# C210_0002_NORA_Module.net
KiCad netlist of a schematic drawn in Altium Designer
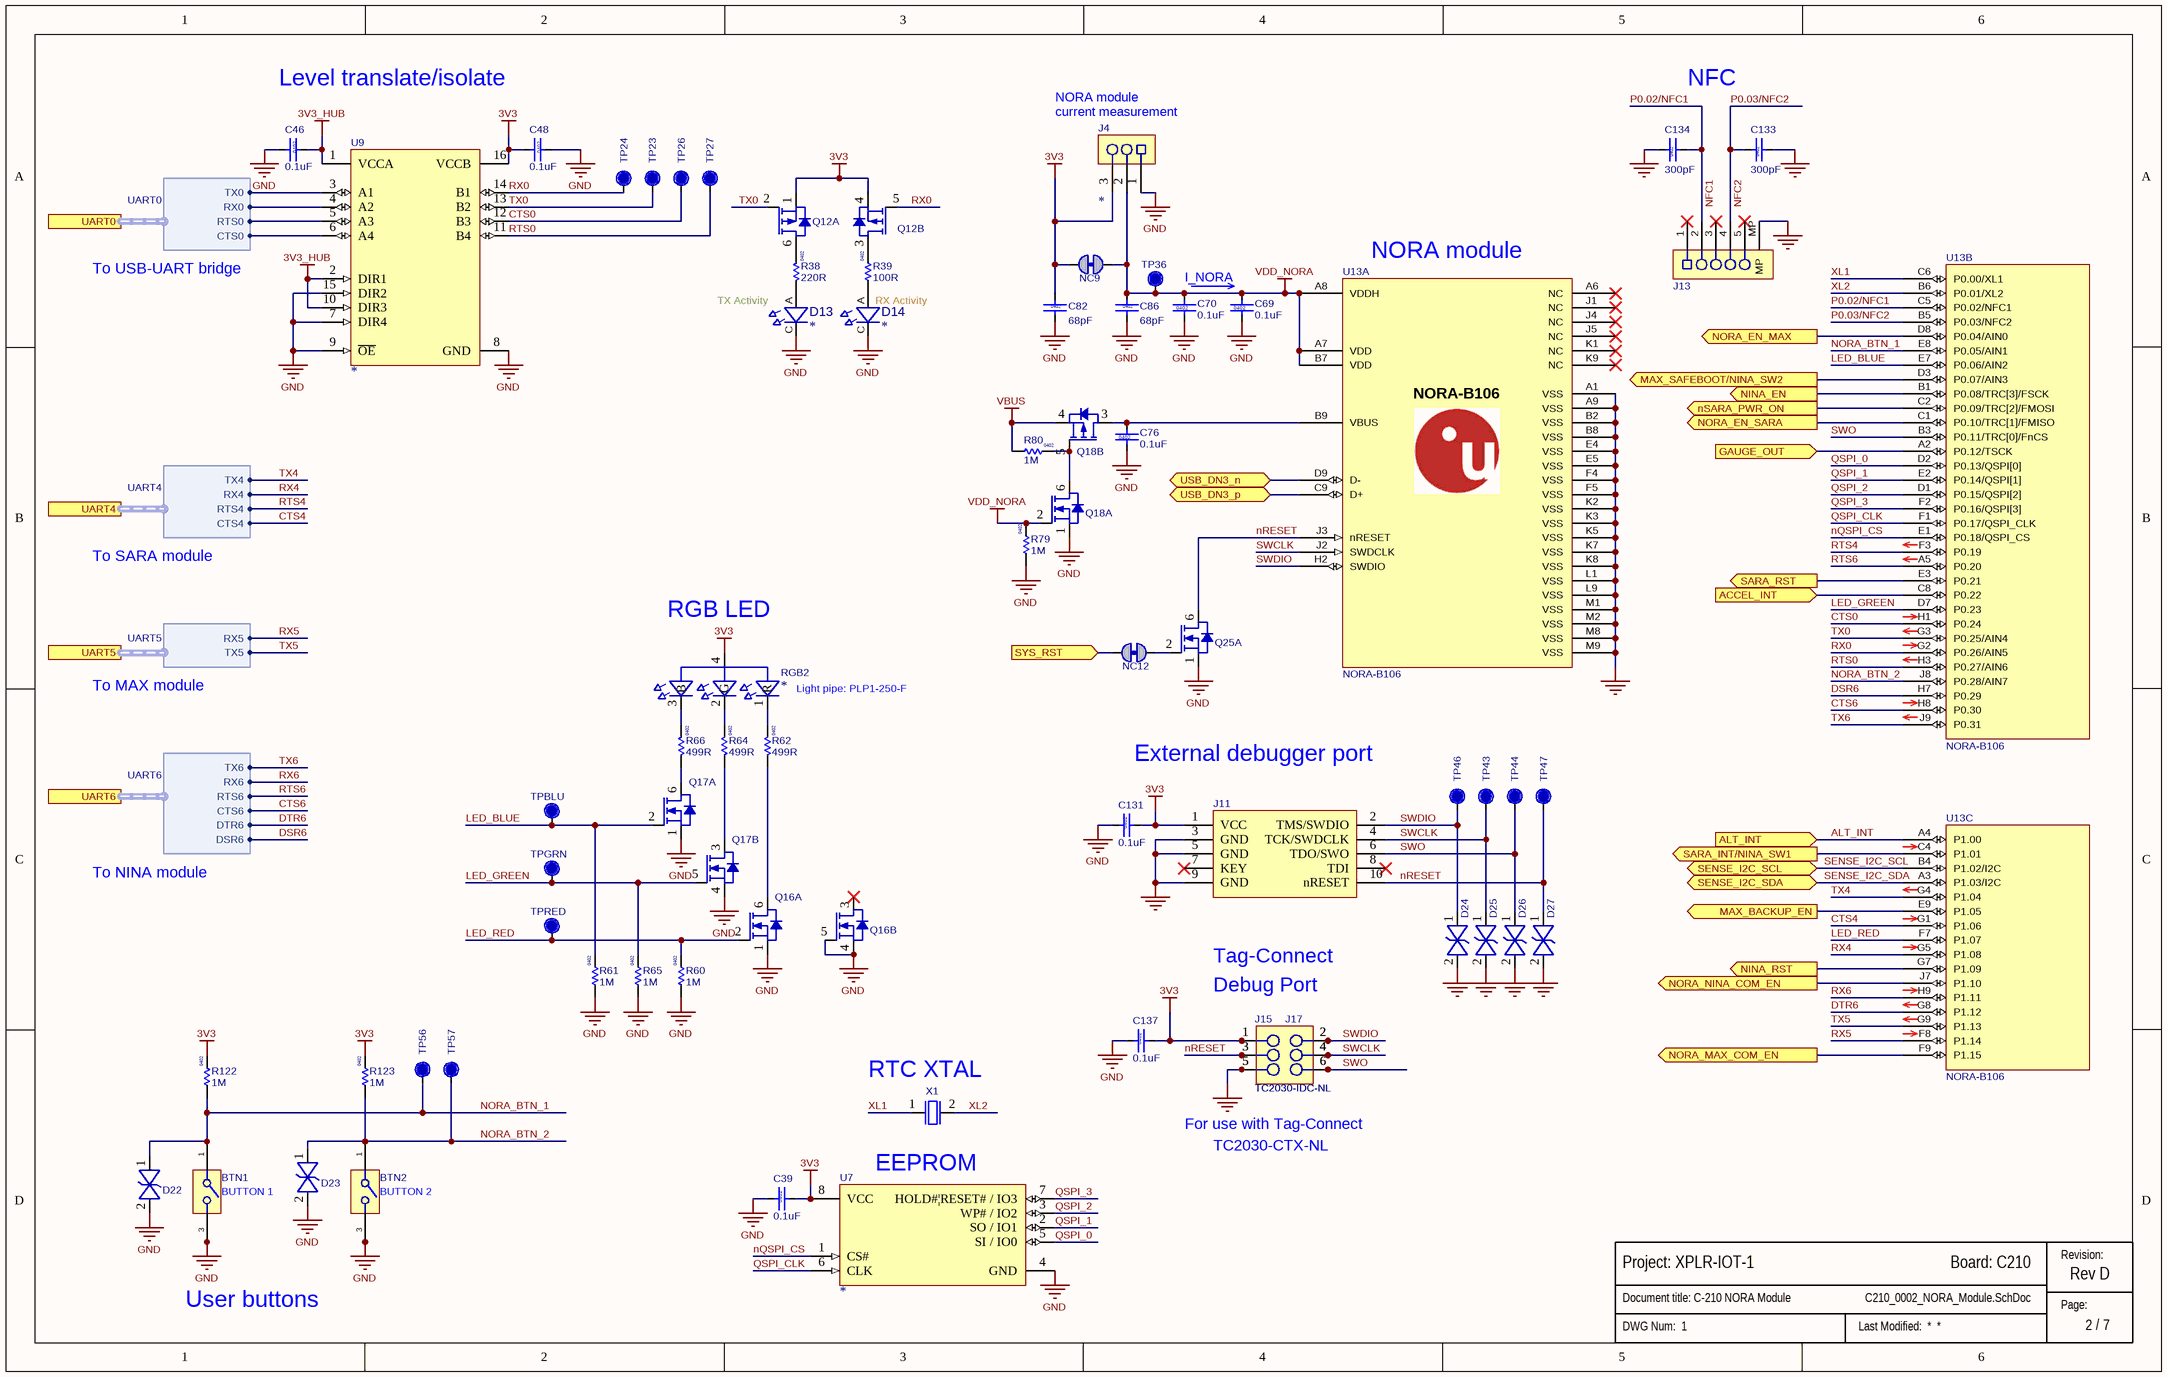
[diagram p0: C210_0002_NORA_Module.SchDoc]

(export (version "E")
  (design (tool "Eeschema 10.0.6"))
  (components
    (comp (ref "BTN1")
      (value "TL6120DF300QG")
      (footprint "TL6120DF300QG")
      (description "Button, Tactile, SPST, NO, SMT, Vert")
      (fields (field (name "VOLTAGE") "None"))
      (libsource (lib "TL6120DF300QG") (part "TL6120DF300QG"))
    )
    (comp (ref "BTN2")
      (value "TL6120DF300QG")
      (footprint "TL6120DF300QG")
      (description "Button, Tactile, SPST, NO, SMT, Vert")
      (fields (field (name "VOLTAGE") "None"))
      (libsource (lib "TL6120DF300QG") (part "TL6120DF300QG"))
    )
    (comp (ref "C39")
      (value "0.1uF")
      (footprint "Cap 0402 HD")
      (description "Cap, Ceramic 0.1uF 10V 10% X5R 0402")
      (fields
        (field (name "SIZE") "0402")
        (field (name "PART NUMBER") "120-00016")
        (field (name "MANUFACTURER") "Murata Electronics North America")
      )
      (libsource (lib "Arena_Parts_DB_Lib") (part "Cap Chip"))
    )
    (comp (ref "C46")
      (value "0.1uF")
      (footprint "Cap 0402 HD")
      (description "Cap, Ceramic 0.1uF 10V 10% X5R 0402")
      (fields
        (field (name "SIZE") "0402")
        (field (name "PART NUMBER") "120-00016")
        (field (name "MANUFACTURER") "Murata Electronics North America")
      )
      (libsource (lib "Arena_Parts_DB_Lib") (part "Cap Chip"))
    )
    (comp (ref "C48")
      (value "0.1uF")
      (footprint "Cap 0402 HD")
      (description "Cap, Ceramic 0.1uF 10V 10% X5R 0402")
      (fields
        (field (name "SIZE") "0402")
        (field (name "PART NUMBER") "120-00016")
        (field (name "MANUFACTURER") "Murata Electronics North America")
      )
      (libsource (lib "Arena_Parts_DB_Lib") (part "Cap Chip"))
    )
    (comp (ref "C69")
      (value "0.1uF")
      (footprint "Cap 0402 HD")
      (description "Cap, Ceramic 0.1uF 10V 10% X5R 0402")
      (fields
        (field (name "SIZE") "0402")
        (field (name "PART NUMBER") "120-00016")
        (field (name "MANUFACTURER") "Murata Electronics North America")
      )
      (libsource (lib "Arena_Parts_DB_Lib") (part "Cap Chip"))
    )
    (comp (ref "C70")
      (value "0.1uF")
      (footprint "Cap 0402 HD")
      (description "Cap, Ceramic 0.1uF 10V 10% X5R 0402")
      (fields
        (field (name "SIZE") "0402")
        (field (name "PART NUMBER") "120-00016")
        (field (name "MANUFACTURER") "Murata Electronics North America")
      )
      (libsource (lib "Arena_Parts_DB_Lib") (part "Cap Chip"))
    )
    (comp (ref "C76")
      (value "0.1uF")
      (footprint "Cap 0402 HD")
      (description "Cap, Ceramic 0.1uF 10V 10% X5R 0402")
      (fields
        (field (name "SIZE") "0402")
        (field (name "PART NUMBER") "120-00016")
        (field (name "MANUFACTURER") "Murata Electronics North America")
      )
      (libsource (lib "Arena_Parts_DB_Lib") (part "Cap Chip"))
    )
    (comp (ref "C82")
      (value "68pF")
      (footprint "Cap 0402 HD")
      (description "Cap, Ceramic, 68pF, 50V, 1%, NP0, 0402")
      (fields
        (field (name "SIZE") "0402")
        (field (name "PART NUMBER") "120-00047")
        (field (name "TOLERANCE") "+/- 1%")
      )
      (libsource (lib "Arena_Parts_DB_Lib") (part "Cap Chip"))
    )
    (comp (ref "C86")
      (value "68pF")
      (footprint "Cap 0402 HD")
      (description "Cap, Ceramic, 68pF, 50V, 1%, NP0, 0402")
      (fields
        (field (name "SIZE") "0402")
        (field (name "PART NUMBER") "120-00047")
        (field (name "TOLERANCE") "+/- 1%")
      )
      (libsource (lib "Arena_Parts_DB_Lib") (part "Cap Chip"))
    )
    (comp (ref "C131")
      (value "0.1uF")
      (footprint "Cap 0402 HD")
      (description "Cap, Ceramic 0.1uF 10V 10% X5R 0402")
      (fields
        (field (name "SIZE") "0402")
        (field (name "PART NUMBER") "120-00016")
        (field (name "MANUFACTURER") "Murata Electronics North America")
      )
      (libsource (lib "Arena_Parts_DB_Lib") (part "Cap Chip"))
    )
    (comp (ref "C133")
      (value "300pF")
      (footprint "Cap 0402 HD")
      (description "Cap, Ceramic 300pF 50V 5% NP0 0402")
      (fields
        (field (name "SIZE") "0402")
        (field (name "PART NUMBER") "120-00099")
        (field (name "MANUFACTURER") "Murata Electronics North America")
      )
      (libsource (lib "Arena_Parts_DB_Lib") (part "Cap Chip"))
    )
    (comp (ref "C134")
      (value "300pF")
      (footprint "Cap 0402 HD")
      (description "Cap, Ceramic 300pF 50V 5% NP0 0402")
      (fields
        (field (name "SIZE") "0402")
        (field (name "PART NUMBER") "120-00099")
        (field (name "MANUFACTURER") "Murata Electronics North America")
      )
      (libsource (lib "Arena_Parts_DB_Lib") (part "Cap Chip"))
    )
    (comp (ref "C137")
      (value "0.1uF")
      (footprint "Cap 0402 HD")
      (description "Cap, Ceramic 0.1uF 10V 10% X5R 0402")
      (fields
        (field (name "SIZE") "0402")
        (field (name "PART NUMBER") "120-00016")
        (field (name "MANUFACTURER") "Murata Electronics North America")
      )
      (libsource (lib "Arena_Parts_DB_Lib") (part "Cap Chip"))
    )
    (comp (ref "D13")
      (value "115-00019")
      (footprint "LTST-C190KGKT")
      (description "DIODE, LED, SMT, GREEN, CLEAR LENS, 2.0V 20mA, 0603")
      (fields (field (name "VOLTAGE") "2.0V") (field (name "COLOR") "*"))
      (libsource (lib "LTST-C190KGKT") (part "LTST-C190KGKT"))
    )
    (comp (ref "D14")
      (value "LTST-C190YKT")
      (footprint "LTST-C190YKT")
      (description "DIODE, LED, SMT, YELLOW, CLEAR LENS, 2.1V 10mA, 0603")
      (fields (field (name "VOLTAGE") "2.1V") (field (name "COLOR") "*"))
      (libsource (lib "LTST-C190YKT") (part "LTST-C190YKT"))
    )
    (comp (ref "D22")
      (value "110-00041")
      (footprint "SOD-523_ALT")
      (description "Diode TVS 5VWM BiDIR SOD523")
      (fields (field (name "VOLTAGE") "5VWM"))
      (libsource (lib "Arena_Parts_DB_Lib") (part "Diode_TVS"))
    )
    (comp (ref "D23")
      (value "110-00041")
      (footprint "SOD-523_ALT")
      (description "Diode TVS 5VWM BiDIR SOD523")
      (fields (field (name "VOLTAGE") "5VWM"))
      (libsource (lib "Arena_Parts_DB_Lib") (part "Diode_TVS"))
    )
    (comp (ref "D24")
      (value "110-00041")
      (footprint "SOD-523_ALT")
      (description "Diode TVS 5VWM BiDIR SOD523")
      (fields (field (name "VOLTAGE") "5VWM"))
      (libsource (lib "Arena_Parts_DB_Lib") (part "Diode_TVS"))
    )
    (comp (ref "D25")
      (value "110-00041")
      (footprint "SOD-523_ALT")
      (description "Diode TVS 5VWM BiDIR SOD523")
      (fields (field (name "VOLTAGE") "5VWM"))
      (libsource (lib "Arena_Parts_DB_Lib") (part "Diode_TVS"))
    )
    (comp (ref "D26")
      (value "110-00041")
      (footprint "SOD-523_ALT")
      (description "Diode TVS 5VWM BiDIR SOD523")
      (fields (field (name "VOLTAGE") "5VWM"))
      (libsource (lib "Arena_Parts_DB_Lib") (part "Diode_TVS"))
    )
    (comp (ref "D27")
      (value "110-00041")
      (footprint "SOD-523_ALT")
      (description "Diode TVS 5VWM BiDIR SOD523")
      (fields (field (name "VOLTAGE") "5VWM"))
      (libsource (lib "Arena_Parts_DB_Lib") (part "Diode_TVS"))
    )
    (comp (ref "J4")
      (value "130-00105")
      (footprint "HDR-0.1P-3Pin-1Row-SMT")
      (description "Header, 0.100\" Pitch, 3 Pin, Vertical SMT, Black")
      (fields (field (name "MANUFACTURER P/N") "*") (field (name "VOLTAGE") "None"))
      (libsource (lib "Arena_Parts_DB_Lib") (part "CON-3Pin_1Row"))
    )
    (comp (ref "J11")
      (value "FTSH-105-01-F-DH-A-C - JTAG")
      (footprint "FTSH-105-01-F-DH-A-C")
      (description "Header 0.05\" 10Pin 2Row SMD, RA, Black")
      (libsource (lib "FTSH-105-01-F-DH-A-C") (part "FTSH-105-01-F-DH-A-C - JTAG"))
    )
    (comp (ref "J13")
      (value "~")
      (footprint "AVX/Kyocera - 046284005001846")
      (description "CON FFC/FPC 0.50mm 5Pos R/A, 046284005001846")
      (fields (field (name "VOLTAGE") "50V"))
      (libsource (lib "046284005001846") (part "CON-5Pin_1Row-046284005001846"))
    )
    (comp (ref "J15")
      (value "TC2030-IDC-NLDNP")
      (footprint "TC2030-IDC-NL")
      (description "CON PADS FOR CBL PLUG-OF-NAILS 6-PIN NO LEGS")
      (fields
        (field (name "PART NUMBER") "TC2030-IDC-NL")
        (field (name "MANUFACTURER") "TAG Connect")
        (field (name "MANUFACTURER P/N") "TC2030-IDC-NL")
        (field (name "ADDED BY") "emoo")
      )
      (libsource (lib "PCB_Misc") (part "CON-6Pin_2Row_ALT"))
    )
    (comp (ref "J17")
      (value "TC2030-IDC-NLDNP")
      (footprint "TC2030-IDC-NL No Hole")
      (description "CON PADS FOR CBL PLUG-OF-NAILS 6-PIN NO LEGS")
      (fields
        (field (name "PART NUMBER") "TC2030-IDC-NL")
        (field (name "MANUFACTURER") "TAG Connect")
        (field (name "MANUFACTURER P/N") "TC2030-IDC-NL")
        (field (name "ADDED BY") "emoo")
      )
      (libsource (lib "PCB_Misc") (part "CON-6Pin_2Row_ALT"))
    )
    (comp (ref "NC9")
      (value "Solderbridge-ShortDNP")
      (footprint "Solderbridge-Short")
      (description "Solderbridge-Short")
      (fields (field (name "ADDED BY") "Paul B"))
      (libsource (lib "PCB_Misc") (part "Solderbridge-Short"))
    )
    (comp (ref "NC12")
      (value "Solderbridge-ShortDNP")
      (footprint "Solderbridge-Short")
      (description "Solderbridge-Short")
      (fields (field (name "ADDED BY") "Paul B"))
      (libsource (lib "PCB_Misc") (part "Solderbridge-Short"))
    )
    (comp (ref "Q12")
      (value "FDY2000PZ")
      (footprint "FDY2000PZ")
      (description "MOSFET DUAL P-CH 20V SOT-563, -350mA")
      (fields (field (name "VOLTAGE") "20V"))
      (libsource (lib "FDY2000PZ") (part "MOSFET-Dual-P_Chan"))
    )
    (comp (ref "Q16")
      (value "140-00016")
      (footprint "SOT-563")
      (description "MOSFET 2N-CH 20V 0.8A, SOT-563")
      (fields (field (name "VOLTAGE") "20V"))
      (libsource (lib "Arena_Parts_DB_Lib") (part "MOSFET-N-Dual"))
    )
    (comp (ref "Q17")
      (value "140-00016")
      (footprint "SOT-563")
      (description "MOSFET 2N-CH 20V 0.8A, SOT-563")
      (fields (field (name "VOLTAGE") "20V"))
      (libsource (lib "Arena_Parts_DB_Lib") (part "MOSFET-N-Dual"))
    )
    (comp (ref "Q18")
      (value "140-00030")
      (footprint "SOT-563")
      (description "MOSFET N/P-CH 20V SOT-563, 540 mA, −430 mA")
      (fields (field (name "VOLTAGE") "20V"))
      (libsource (lib "Arena_Parts_DB_Lib") (part "MOSFET-N-P_Pair"))
    )
    (comp (ref "Q25")
      (value "140-00016")
      (footprint "SOT-563")
      (description "MOSFET 2N-CH 20V 0.8A, SOT-563")
      (fields (field (name "VOLTAGE") "20V"))
      (libsource (lib "Arena_Parts_DB_Lib") (part "MOSFET-N-Dual"))
    )
    (comp (ref "R38")
      (value "220R")
      (footprint "RES 0402 HD")
      (description "Resistor, 220ohm, 5%, 1/16W, 0402.")
      (fields
        (field (name "SIZE") "0402")
        (field (name "PART NUMBER") "180-00098")
        (field (name "MANUFACTURER") "Panasonic Electronic Components")
      )
      (libsource (lib "Arena_Parts_DB_Lib") (part "Res sm"))
    )
    (comp (ref "R39")
      (value "100R")
      (footprint "RES 0402 HD")
      (description "Resistor, 100ohm, 1%, 1/16W, 0402.")
      (fields
        (field (name "SIZE") "0402")
        (field (name "PART NUMBER") "180-00051")
        (field (name "POWER") "1/16W")
      )
      (libsource (lib "Arena_Parts_DB_Lib") (part "Res sm"))
    )
    (comp (ref "R60")
      (value "1M")
      (footprint "RES 0402 HD")
      (description "Resistor 1M ohm 1%, 1/16W, 0402")
      (fields
        (field (name "SIZE") "0402")
        (field (name "PART NUMBER") "180-00054")
        (field (name "POWER") "1/16W")
      )
      (libsource (lib "Arena_Parts_DB_Lib") (part "Res sm"))
    )
    (comp (ref "R61")
      (value "1M")
      (footprint "RES 0402 HD")
      (description "Resistor 1M ohm 1%, 1/16W, 0402")
      (fields
        (field (name "SIZE") "0402")
        (field (name "PART NUMBER") "180-00054")
        (field (name "POWER") "1/16W")
      )
      (libsource (lib "Arena_Parts_DB_Lib") (part "Res sm"))
    )
    (comp (ref "R62")
      (value "499R")
      (footprint "RES 0402 HD")
      (description "Resistor, 499ohm, 1%, 1/16W, 0402")
      (fields
        (field (name "SIZE") "0402")
        (field (name "PART NUMBER") "180-00031")
        (field (name "MANUFACTURER") "Rohm Semiconductor")
      )
      (libsource (lib "Arena_Parts_DB_Lib") (part "Res sm"))
    )
    (comp (ref "R64")
      (value "499R")
      (footprint "RES 0402 HD")
      (description "Resistor, 499ohm, 1%, 1/16W, 0402")
      (fields
        (field (name "SIZE") "0402")
        (field (name "PART NUMBER") "180-00031")
        (field (name "MANUFACTURER") "Rohm Semiconductor")
      )
      (libsource (lib "Arena_Parts_DB_Lib") (part "Res sm"))
    )
    (comp (ref "R65")
      (value "1M")
      (footprint "RES 0402 HD")
      (description "Resistor 1M ohm 1%, 1/16W, 0402")
      (fields
        (field (name "SIZE") "0402")
        (field (name "PART NUMBER") "180-00054")
        (field (name "POWER") "1/16W")
      )
      (libsource (lib "Arena_Parts_DB_Lib") (part "Res sm"))
    )
    (comp (ref "R66")
      (value "499R")
      (footprint "RES 0402 HD")
      (description "Resistor, 499ohm, 1%, 1/16W, 0402")
      (fields
        (field (name "SIZE") "0402")
        (field (name "PART NUMBER") "180-00031")
        (field (name "MANUFACTURER") "Rohm Semiconductor")
      )
      (libsource (lib "Arena_Parts_DB_Lib") (part "Res sm"))
    )
    (comp (ref "R79")
      (value "1M")
      (footprint "RES 0402 HD")
      (description "Resistor 1M ohm 1%, 1/16W, 0402")
      (fields
        (field (name "SIZE") "0402")
        (field (name "PART NUMBER") "180-00054")
        (field (name "POWER") "1/16W")
      )
      (libsource (lib "Arena_Parts_DB_Lib") (part "Res sm"))
    )
    (comp (ref "R80")
      (value "1M")
      (footprint "RES 0402 HD")
      (description "Resistor 1M ohm 1%, 1/16W, 0402")
      (fields
        (field (name "SIZE") "0402")
        (field (name "PART NUMBER") "180-00054")
        (field (name "POWER") "1/16W")
      )
      (libsource (lib "Arena_Parts_DB_Lib") (part "Res sm"))
    )
    (comp (ref "R122")
      (value "1M")
      (footprint "RES 0402 HD")
      (description "Resistor 1M ohm 1%, 1/16W, 0402")
      (fields
        (field (name "SIZE") "0402")
        (field (name "PART NUMBER") "180-00054")
        (field (name "POWER") "1/16W")
      )
      (libsource (lib "Arena_Parts_DB_Lib") (part "Res sm"))
    )
    (comp (ref "R123")
      (value "1M")
      (footprint "RES 0402 HD")
      (description "Resistor 1M ohm 1%, 1/16W, 0402")
      (fields
        (field (name "SIZE") "0402")
        (field (name "PART NUMBER") "180-00054")
        (field (name "POWER") "1/16W")
      )
      (libsource (lib "Arena_Parts_DB_Lib") (part "Res sm"))
    )
    (comp (ref "RGB2")
      (value "115-00026")
      (footprint "LED_1616")
      (description "LED RGB SMT 0606")
      (fields (field (name "COLOR") "*") (field (name "VOLTAGE") "None"))
      (libsource (lib "Arena_Parts_DB_Lib") (part "LED_RGB_CA_4"))
    )
    (comp (ref "TP23")
      (value "TP")
      (footprint "TP12R")
      (description "Testpoint, Round 1.0mm Dia")
      (fields
        (field (name "PART NUMBER") "TP10R")
        (field (name "ADDED BY") "Jeremy D")
        (field (name "CHECKED BY") "Paul B")
      )
      (libsource (lib "PCB_Misc") (part "TP_R"))
    )
    (comp (ref "TP24")
      (value "TP")
      (footprint "TP12R")
      (description "Testpoint, Round 1.0mm Dia")
      (fields
        (field (name "PART NUMBER") "TP10R")
        (field (name "ADDED BY") "Jeremy D")
        (field (name "CHECKED BY") "Paul B")
      )
      (libsource (lib "PCB_Misc") (part "TP_R"))
    )
    (comp (ref "TP26")
      (value "TP")
      (footprint "TP12R")
      (description "Testpoint, Round 1.0mm Dia")
      (fields
        (field (name "PART NUMBER") "TP10R")
        (field (name "ADDED BY") "Jeremy D")
        (field (name "CHECKED BY") "Paul B")
      )
      (libsource (lib "PCB_Misc") (part "TP_R"))
    )
    (comp (ref "TP27")
      (value "TP")
      (footprint "TP12R")
      (description "Testpoint, Round 1.0mm Dia")
      (fields
        (field (name "PART NUMBER") "TP10R")
        (field (name "ADDED BY") "Jeremy D")
        (field (name "CHECKED BY") "Paul B")
      )
      (libsource (lib "PCB_Misc") (part "TP_R"))
    )
    (comp (ref "TP36")
      (value "TP")
      (footprint "TP12R")
      (description "Testpoint, Round 1.0mm Dia")
      (fields
        (field (name "PART NUMBER") "TP10R")
        (field (name "ADDED BY") "Jeremy D")
        (field (name "CHECKED BY") "Paul B")
      )
      (libsource (lib "PCB_Misc") (part "TP_R"))
    )
    (comp (ref "TP43")
      (value "TP")
      (footprint "TP12R")
      (description "Testpoint, Round 1.0mm Dia")
      (fields
        (field (name "PART NUMBER") "TP10R")
        (field (name "ADDED BY") "Jeremy D")
        (field (name "CHECKED BY") "Paul B")
      )
      (libsource (lib "PCB_Misc") (part "TP_R"))
    )
    (comp (ref "TP44")
      (value "TP")
      (footprint "TP12R")
      (description "Testpoint, Round 1.0mm Dia")
      (fields
        (field (name "PART NUMBER") "TP10R")
        (field (name "ADDED BY") "Jeremy D")
        (field (name "CHECKED BY") "Paul B")
      )
      (libsource (lib "PCB_Misc") (part "TP_R"))
    )
    (comp (ref "TP46")
      (value "TP")
      (footprint "TP12R")
      (description "Testpoint, Round 1.0mm Dia")
      (fields
        (field (name "PART NUMBER") "TP10R")
        (field (name "ADDED BY") "Jeremy D")
        (field (name "CHECKED BY") "Paul B")
      )
      (libsource (lib "PCB_Misc") (part "TP_R"))
    )
    (comp (ref "TP47")
      (value "TP")
      (footprint "TP12R")
      (description "Testpoint, Round 1.0mm Dia")
      (fields
        (field (name "PART NUMBER") "TP10R")
        (field (name "ADDED BY") "Jeremy D")
        (field (name "CHECKED BY") "Paul B")
      )
      (libsource (lib "PCB_Misc") (part "TP_R"))
    )
    (comp (ref "TP56")
      (value "TP")
      (footprint "TP12R")
      (description "Testpoint, Round 1.0mm Dia")
      (fields
        (field (name "PART NUMBER") "TP10R")
        (field (name "ADDED BY") "Jeremy D")
        (field (name "CHECKED BY") "Paul B")
      )
      (libsource (lib "PCB_Misc") (part "TP_R"))
    )
    (comp (ref "TP57")
      (value "TP")
      (footprint "TP12R")
      (description "Testpoint, Round 1.0mm Dia")
      (fields
        (field (name "PART NUMBER") "TP10R")
        (field (name "ADDED BY") "Jeremy D")
        (field (name "CHECKED BY") "Paul B")
      )
      (libsource (lib "PCB_Misc") (part "TP_R"))
    )
    (comp (ref "TPBLU")
      (value "TP")
      (footprint "TP12R")
      (description "Testpoint, Round 1.0mm Dia")
      (fields
        (field (name "PART NUMBER") "TP10R")
        (field (name "ADDED BY") "Jeremy D")
        (field (name "CHECKED BY") "Paul B")
      )
      (libsource (lib "PCB_Misc") (part "TP_R"))
    )
    (comp (ref "TPGRN")
      (value "TP")
      (footprint "TP12R")
      (description "Testpoint, Round 1.0mm Dia")
      (fields
        (field (name "PART NUMBER") "TP10R")
        (field (name "ADDED BY") "Jeremy D")
        (field (name "CHECKED BY") "Paul B")
      )
      (libsource (lib "PCB_Misc") (part "TP_R"))
    )
    (comp (ref "TPRED")
      (value "TP")
      (footprint "TP12R")
      (description "Testpoint, Round 1.0mm Dia")
      (fields
        (field (name "PART NUMBER") "TP10R")
        (field (name "ADDED BY") "Jeremy D")
        (field (name "CHECKED BY") "Paul B")
      )
      (libsource (lib "PCB_Misc") (part "TP_R"))
    )
    (comp (ref "U7")
      (value "240-00033")
      (footprint "WSON1.27P-8Pin_W-Pad")
      (description "64Mbit QSPI NOR Flash")
      (fields (field (name "MANUFACTURER P/N") "*") (field (name "VOLTAGE") "3.6V"))
      (libsource (lib "Arena_Parts_DB_Lib") (part "SPI_Flash_Memory_8Pin"))
    )
    (comp (ref "U9")
      (value "225-00011")
      (footprint "QFN0.5P2x6-16Pin_W-Pad")
      (description "Voltage Level Translator Bidirectional 1 Circuit 4 Channel 380Mbps 16-DHVQFN (2.5x3.5)")
      (fields (field (name "MANUFACTURER P/N") "*") (field (name "VOLTAGE") "3.6V"))
      (libsource (lib "Arena_Parts_DB_Lib") (part "74AVC4TD245"))
    )
    (comp (ref "U13")
      (value "NORA-B106")
      (footprint "NORA_LGA82R_1430X1040X180_ANT")
      (description "u-blox NORA-B106 Bluetooth 5.2 LE module - dual core")
      (fields (field (name "MANUFACTURER") "u-blox"))
      (libsource (lib "NORA") (part "NORA-B106"))
    )
    (comp (ref "X1")
      (value "100-00005")
      (footprint "XTAL_3215")
      (description "XTAL, 2Pin, 32.768kHz, 7pF 20ppm")
      (libsource (lib "Arena_Parts_DB_Lib") (part "XTAL_2Pin"))
    )
  )
  (nets
    (net (code "5") (name "/ACCEL_INT") (class "Default")
      (node (ref "U13") (pin "C8") (pinfunction "P0.22_C8") (pintype "bidirectional"))
    )
    (net (code "6") (name "/ALT_INT") (class "Default")
      (node (ref "U13") (pin "A4") (pinfunction "P1.00_A4") (pintype "bidirectional"))
    )
    (net (code "7") (name "/CTS0") (class "Default")
      (node (ref "TP26") (pin "1") (pintype "passive"))
      (node (ref "U13") (pin "H1") (pinfunction "P0.24_H1") (pintype "bidirectional"))
      (node (ref "U9") (pin "12") (pinfunction "B3_12") (pintype "bidirectional"))
    )
    (net (code "8") (name "/CTS4") (class "Default")
      (node (ref "U13") (pin "G1") (pinfunction "P1.06_G1") (pintype "bidirectional"))
    )
    (net (code "9") (name "/CTS6") (class "Default")
      (node (ref "U13") (pin "H8") (pinfunction "P0.30_H8") (pintype "bidirectional"))
    )
    (net (code "10") (name "/DSR6") (class "Default")
      (node (ref "U13") (pin "H7") (pinfunction "P0.29_H7") (pintype "bidirectional"))
    )
    (net (code "11") (name "/DTR6") (class "Default")
      (node (ref "U13") (pin "G8") (pinfunction "P1.12_G8") (pintype "bidirectional"))
    )
    (net (code "12") (name "/GAUGE_OUT") (class "Default")
      (node (ref "U13") (pin "A2") (pinfunction "P0.12/TSCK_A2") (pintype "bidirectional"))
    )
    (net (code "13") (name "/LED_BLUE") (class "Default")
      (node (ref "Q17") (pin "2") (pinfunction "G1_2") (pintype "passive"))
      (node (ref "R61") (pin "2") (pinfunction "2_2") (pintype "passive"))
      (node (ref "TPBLU") (pin "1") (pintype "passive"))
      (node (ref "U13") (pin "E7") (pinfunction "P0.06/AIN2_E7") (pintype "bidirectional"))
    )
    (net (code "14") (name "/LED_GREEN") (class "Default")
      (node (ref "Q17") (pin "5") (pinfunction "G2_5") (pintype "passive"))
      (node (ref "R65") (pin "2") (pinfunction "2_2") (pintype "passive"))
      (node (ref "TPGRN") (pin "1") (pintype "passive"))
      (node (ref "U13") (pin "D7") (pinfunction "P0.23_D7") (pintype "bidirectional"))
    )
    (net (code "15") (name "/LED_RED") (class "Default")
      (node (ref "Q16") (pin "2") (pinfunction "G1_2") (pintype "passive"))
      (node (ref "R60") (pin "2") (pinfunction "2_2") (pintype "passive"))
      (node (ref "TPRED") (pin "1") (pintype "passive"))
      (node (ref "U13") (pin "F7") (pinfunction "P1.07_F7") (pintype "bidirectional"))
    )
    (net (code "16") (name "/MAX_BACKUP_EN") (class "Default")
      (node (ref "U13") (pin "E9") (pinfunction "P1.05_E9") (pintype "bidirectional"))
    )
    (net (code "17") (name "/MAX_SAFEBOOT{slash}NINA_SW2") (class "Default")
      (node (ref "U13") (pin "D3") (pinfunction "P0.07/AIN3_D3") (pintype "bidirectional"))
    )
    (net (code "18") (name "/NFC1") (class "Default")
      (node (ref "C134") (pin "2") (pinfunction "2_2") (pintype "passive"))
      (node (ref "J13") (pin "2") (pinfunction "2_2") (pintype "passive"))
      (node (ref "U13") (pin "C5") (pinfunction "P0.02/NFC1_C5") (pintype "bidirectional"))
    )
    (net (code "19") (name "/NFC2") (class "Default")
      (node (ref "C133") (pin "1") (pinfunction "1_1") (pintype "passive"))
      (node (ref "J13") (pin "4") (pinfunction "4_4") (pintype "passive"))
      (node (ref "U13") (pin "B5") (pinfunction "P0.03/NFC2_B5") (pintype "bidirectional"))
    )
    (net (code "20") (name "/NINA_EN") (class "Default")
      (node (ref "U13") (pin "B1") (pinfunction "P0.08/TRC[3]/FSCK_B1") (pintype "bidirectional"))
    )
    (net (code "21") (name "/NINA_RST") (class "Default")
      (node (ref "U13") (pin "G7") (pinfunction "P1.09_G7") (pintype "bidirectional"))
    )
    (net (code "22") (name "/NORA_BTN_1") (class "Default")
      (node (ref "BTN1") (pin "1") (pinfunction "1_1") (pintype "passive"))
      (node (ref "BTN1") (pin "2") (pinfunction "2_2") (pintype "passive"))
      (node (ref "D22") (pin "1") (pintype "passive"))
      (node (ref "R122") (pin "1") (pinfunction "1_1") (pintype "passive"))
      (node (ref "TP56") (pin "1") (pintype "passive"))
      (node (ref "U13") (pin "E8") (pinfunction "P0.05/AIN1_E8") (pintype "bidirectional"))
    )
    (net (code "23") (name "/NORA_BTN_2") (class "Default")
      (node (ref "BTN2") (pin "1") (pinfunction "1_1") (pintype "passive"))
      (node (ref "BTN2") (pin "2") (pinfunction "2_2") (pintype "passive"))
      (node (ref "D23") (pin "1") (pintype "passive"))
      (node (ref "R123") (pin "1") (pinfunction "1_1") (pintype "passive"))
      (node (ref "TP57") (pin "1") (pintype "passive"))
      (node (ref "U13") (pin "J8") (pinfunction "P0.28/AIN7_J8") (pintype "bidirectional"))
    )
    (net (code "24") (name "/NORA_EN_MAX") (class "Default")
      (node (ref "U13") (pin "D8") (pinfunction "P0.04/AIN0_D8") (pintype "bidirectional"))
    )
    (net (code "25") (name "/NORA_EN_SARA") (class "Default")
      (node (ref "U13") (pin "C1") (pinfunction "P0.10/TRC[1]/FMISO_C1") (pintype "bidirectional"))
    )
    (net (code "26") (name "/NORA_MAX_COM_EN") (class "Default")
      (node (ref "U13") (pin "F9") (pinfunction "P1.15_F9") (pintype "bidirectional"))
    )
    (net (code "27") (name "/NORA_NINA_COM_EN") (class "Default")
      (node (ref "U13") (pin "J7") (pinfunction "P1.10_J7") (pintype "bidirectional"))
    )
    (net (code "28") (name "/QSPI_0") (class "Default")
      (node (ref "U13") (pin "D2") (pinfunction "P0.13/QSPI[0]_D2") (pintype "bidirectional"))
      (node (ref "U7") (pin "5") (pinfunction "SI_/_IO0_5") (pintype "bidirectional"))
    )
    (net (code "29") (name "/QSPI_1") (class "Default")
      (node (ref "U13") (pin "E2") (pinfunction "P0.14/QSPI[1]_E2") (pintype "bidirectional"))
      (node (ref "U7") (pin "2") (pinfunction "SO_/_IO1_2") (pintype "bidirectional"))
    )
    (net (code "30") (name "/QSPI_2") (class "Default")
      (node (ref "U13") (pin "D1") (pinfunction "P0.15/QSPI[2]_D1") (pintype "bidirectional"))
      (node (ref "U7") (pin "3") (pinfunction "WP#_/_IO2_3") (pintype "bidirectional"))
    )
    (net (code "31") (name "/QSPI_3") (class "Default")
      (node (ref "U13") (pin "F2") (pinfunction "P0.16/QSPI[3]_F2") (pintype "bidirectional"))
      (node (ref "U7") (pin "7") (pinfunction "HOLD#¦RESET#_/_IO3_7") (pintype "bidirectional"))
    )
    (net (code "32") (name "/QSPI_CLK") (class "Default")
      (node (ref "U13") (pin "F1") (pinfunction "P0.17/QSPI_CLK_F1") (pintype "bidirectional"))
      (node (ref "U7") (pin "6") (pinfunction "CLK_6") (pintype "input"))
    )
    (net (code "33") (name "/RTS0") (class "Default")
      (node (ref "TP27") (pin "1") (pintype "passive"))
      (node (ref "U13") (pin "H3") (pinfunction "P0.27/AIN6_H3") (pintype "bidirectional"))
      (node (ref "U9") (pin "11") (pinfunction "B4_11") (pintype "bidirectional"))
    )
    (net (code "34") (name "/RTS4") (class "Default")
      (node (ref "U13") (pin "F3") (pinfunction "P0.19_F3") (pintype "bidirectional"))
    )
    (net (code "35") (name "/RTS6") (class "Default")
      (node (ref "U13") (pin "A5") (pinfunction "P0.20_A5") (pintype "bidirectional"))
    )
    (net (code "36") (name "/RX0") (class "Default")
      (node (ref "Q12") (pin "5") (pinfunction "G2_5") (pintype "passive"))
      (node (ref "TP24") (pin "1") (pintype "passive"))
      (node (ref "U13") (pin "G2") (pinfunction "P0.26/AIN5_G2") (pintype "bidirectional"))
      (node (ref "U9") (pin "14") (pinfunction "B1_14") (pintype "bidirectional"))
    )
    (net (code "37") (name "/RX4") (class "Default")
      (node (ref "U13") (pin "G5") (pinfunction "P1.08_G5") (pintype "bidirectional"))
    )
    (net (code "38") (name "/RX5") (class "Default")
      (node (ref "U13") (pin "F8") (pinfunction "P1.14_F8") (pintype "bidirectional"))
    )
    (net (code "39") (name "/RX6") (class "Default")
      (node (ref "U13") (pin "H9") (pinfunction "P1.11_H9") (pintype "bidirectional"))
    )
    (net (code "40") (name "/SARA_INT{slash}NINA_SW1") (class "Default")
      (node (ref "U13") (pin "C4") (pinfunction "P1.01_C4") (pintype "bidirectional"))
    )
    (net (code "41") (name "/SARA_RST") (class "Default")
      (node (ref "U13") (pin "E3") (pinfunction "P0.21_E3") (pintype "bidirectional"))
    )
    (net (code "42") (name "/SENSE_I2C_SCL") (class "Default")
      (node (ref "U13") (pin "B4") (pinfunction "P1.02/I2C_B4") (pintype "bidirectional"))
    )
    (net (code "43") (name "/SENSE_I2C_SDA") (class "Default")
      (node (ref "U13") (pin "A3") (pinfunction "P1.03/I2C_A3") (pintype "bidirectional"))
    )
    (net (code "44") (name "/SWCLK") (class "Default")
      (node (ref "D25") (pin "1") (pintype "passive"))
      (node (ref "J11") (pin "4") (pinfunction "TCK/SWDCLK_4") (pintype "passive"))
      (node (ref "J15") (pin "4") (pintype "passive"))
      (node (ref "J17") (pin "4") (pintype "passive"))
      (node (ref "TP43") (pin "1") (pintype "passive"))
      (node (ref "U13") (pin "J2") (pinfunction "SWDCLK_J2") (pintype "input"))
    )
    (net (code "45") (name "/SWDIO") (class "Default")
      (node (ref "D24") (pin "1") (pintype "passive"))
      (node (ref "J11") (pin "2") (pinfunction "TMS/SWDIO_2") (pintype "passive"))
      (node (ref "J15") (pin "2") (pintype "passive"))
      (node (ref "J17") (pin "2") (pintype "passive"))
      (node (ref "TP46") (pin "1") (pintype "passive"))
      (node (ref "U13") (pin "H2") (pinfunction "SWDIO_H2") (pintype "bidirectional"))
    )
    (net (code "46") (name "/SWO") (class "Default")
      (node (ref "D26") (pin "1") (pintype "passive"))
      (node (ref "J11") (pin "6") (pinfunction "TDO/SWO_6") (pintype "passive"))
      (node (ref "J15") (pin "6") (pintype "passive"))
      (node (ref "J17") (pin "6") (pintype "passive"))
      (node (ref "TP44") (pin "1") (pintype "passive"))
      (node (ref "U13") (pin "B3") (pinfunction "P0.11/TRC[0]/FnCS_B3") (pintype "bidirectional"))
    )
    (net (code "47") (name "/SYS_RST") (class "Default")
      (node (ref "NC12") (pin "2") (pinfunction "2_2") (pintype "passive"))
    )
    (net (code "48") (name "/TX0") (class "Default")
      (node (ref "Q12") (pin "2") (pinfunction "G1_2") (pintype "passive"))
      (node (ref "TP23") (pin "1") (pintype "passive"))
      (node (ref "U13") (pin "G3") (pinfunction "P0.25/AIN4_G3") (pintype "bidirectional"))
      (node (ref "U9") (pin "13") (pinfunction "B2_13") (pintype "bidirectional"))
    )
    (net (code "49") (name "/TX4") (class "Default")
      (node (ref "U13") (pin "G4") (pinfunction "P1.04_G4") (pintype "bidirectional"))
    )
    (net (code "50") (name "/TX5") (class "Default")
      (node (ref "U13") (pin "G9") (pinfunction "P1.13_G9") (pintype "bidirectional"))
    )
    (net (code "51") (name "/TX6") (class "Default")
      (node (ref "U13") (pin "J9") (pinfunction "P0.31_J9") (pintype "bidirectional"))
    )
    (net (code "52") (name "/USB_DN3_n") (class "Default")
      (node (ref "U13") (pin "D9") (pinfunction "D-_D9") (pintype "bidirectional"))
    )
    (net (code "53") (name "/USB_DN3_p") (class "Default")
      (node (ref "U13") (pin "C9") (pinfunction "D+_C9") (pintype "bidirectional"))
    )
    (net (code "54") (name "/XL1") (class "Default")
      (node (ref "U13") (pin "C6") (pinfunction "P0.00/XL1_C6") (pintype "bidirectional"))
      (node (ref "X1") (pin "1") (pintype "passive"))
    )
    (net (code "55") (name "/XL2") (class "Default")
      (node (ref "U13") (pin "B6") (pinfunction "P0.01/XL2_B6") (pintype "bidirectional"))
      (node (ref "X1") (pin "2") (pintype "passive"))
    )
    (net (code "56") (name "/nQSPI_CS") (class "Default")
      (node (ref "U13") (pin "E1") (pinfunction "P0.18/QSPI_CS_E1") (pintype "bidirectional"))
      (node (ref "U7") (pin "1") (pinfunction "CS#_1") (pintype "input"))
    )
    (net (code "57") (name "/nRESET") (class "Default")
      (node (ref "D27") (pin "1") (pintype "passive"))
      (node (ref "J11") (pin "10") (pinfunction "nRESET_10") (pintype "passive"))
      (node (ref "J15") (pin "3") (pintype "passive"))
      (node (ref "J17") (pin "3") (pintype "passive"))
      (node (ref "Q25") (pin "6") (pinfunction "D1_6") (pintype "passive"))
      (node (ref "TP47") (pin "1") (pintype "passive"))
      (node (ref "U13") (pin "J3") (pinfunction "nRESET_J3") (pintype "input"))
    )
    (net (code "58") (name "/nSARA_PWR_ON") (class "Default")
      (node (ref "U13") (pin "C2") (pinfunction "P0.09/TRC[2]/FMOSI_C2") (pintype "bidirectional"))
    )
    (net (code "63") (name "3V3") (class "Default")
      (node (ref "C131") (pin "2") (pinfunction "2_2") (pintype "passive"))
      (node (ref "C137") (pin "2") (pinfunction "2_2") (pintype "passive"))
      (node (ref "C39") (pin "2") (pinfunction "2_2") (pintype "passive"))
      (node (ref "C48") (pin "2") (pinfunction "2_2") (pintype "passive"))
      (node (ref "C82") (pin "1") (pinfunction "1_1") (pintype "passive"))
      (node (ref "J11") (pin "1") (pinfunction "VCC_1") (pintype "passive"))
      (node (ref "J15") (pin "1") (pintype "passive"))
      (node (ref "J17") (pin "1") (pintype "passive"))
      (node (ref "J4") (pin "3") (pinfunction "3_3") (pintype "passive"))
      (node (ref "NC9") (pin "2") (pinfunction "2_2") (pintype "passive"))
      (node (ref "Q12") (pin "1") (pinfunction "S1_1") (pintype "passive"))
      (node (ref "Q12") (pin "4") (pinfunction "S2_4") (pintype "passive"))
      (node (ref "R122") (pin "2") (pinfunction "2_2") (pintype "passive"))
      (node (ref "R123") (pin "2") (pinfunction "2_2") (pintype "passive"))
      (node (ref "RGB2") (pin "4") (pinfunction "A_4") (pintype "passive"))
      (node (ref "U7") (pin "8") (pinfunction "VCC_8") (pintype "power_in"))
      (node (ref "U9") (pin "16") (pinfunction "VCCB_16") (pintype "power_in"))
    )
    (net (code "64") (name "3V3_HUB") (class "Default")
      (node (ref "C46") (pin "1") (pinfunction "1_1") (pintype "passive"))
      (node (ref "U9") (pin "1") (pinfunction "VCCA_1") (pintype "power_in"))
      (node (ref "U9") (pin "10") (pinfunction "DIR3_10") (pintype "input"))
      (node (ref "U9") (pin "2") (pinfunction "DIR1_2") (pintype "input"))
    )
    (net (code "65") (name "GND") (class "Default")
      (node (ref "BTN1") (pin "3") (pinfunction "3_3") (pintype "passive"))
      (node (ref "BTN1") (pin "4") (pinfunction "4_4") (pintype "passive"))
      (node (ref "BTN2") (pin "3") (pinfunction "3_3") (pintype "passive"))
      (node (ref "BTN2") (pin "4") (pinfunction "4_4") (pintype "passive"))
      (node (ref "C131") (pin "1") (pinfunction "1_1") (pintype "passive"))
      (node (ref "C133") (pin "2") (pinfunction "2_2") (pintype "passive"))
      (node (ref "C134") (pin "1") (pinfunction "1_1") (pintype "passive"))
      (node (ref "C137") (pin "1") (pinfunction "1_1") (pintype "passive"))
      (node (ref "C39") (pin "1") (pinfunction "1_1") (pintype "passive"))
      (node (ref "C46") (pin "2") (pinfunction "2_2") (pintype "passive"))
      (node (ref "C48") (pin "1") (pinfunction "1_1") (pintype "passive"))
      (node (ref "C69") (pin "1") (pinfunction "1_1") (pintype "passive"))
      (node (ref "C70") (pin "1") (pinfunction "1_1") (pintype "passive"))
      (node (ref "C76") (pin "1") (pinfunction "1_1") (pintype "passive"))
      (node (ref "C82") (pin "2") (pinfunction "2_2") (pintype "passive"))
      (node (ref "C86") (pin "2") (pinfunction "2_2") (pintype "passive"))
      (node (ref "D13") (pin "C") (pinfunction "Cathode_C") (pintype "passive"))
      (node (ref "D14") (pin "C") (pinfunction "Cathode_C") (pintype "passive"))
      (node (ref "D22") (pin "2") (pintype "passive"))
      (node (ref "D23") (pin "2") (pintype "passive"))
      (node (ref "D24") (pin "2") (pintype "passive"))
      (node (ref "D25") (pin "2") (pintype "passive"))
      (node (ref "D26") (pin "2") (pintype "passive"))
      (node (ref "D27") (pin "2") (pintype "passive"))
      (node (ref "J11") (pin "3") (pinfunction "GND_3") (pintype "passive"))
      (node (ref "J11") (pin "5") (pinfunction "GND_5") (pintype "passive"))
      (node (ref "J11") (pin "9") (pinfunction "GND_9") (pintype "passive"))
      (node (ref "J13") (pin "MP") (pinfunction "MP_MP") (pintype "passive"))
      (node (ref "J15") (pin "5") (pintype "passive"))
      (node (ref "J17") (pin "5") (pintype "passive"))
      (node (ref "J4") (pin "1") (pinfunction "1_1") (pintype "passive"))
      (node (ref "Q16") (pin "1") (pinfunction "S1_1") (pintype "passive"))
      (node (ref "Q16") (pin "4") (pinfunction "S2_4") (pintype "passive"))
      (node (ref "Q16") (pin "5") (pinfunction "G2_5") (pintype "passive"))
      (node (ref "Q17") (pin "1") (pinfunction "S1_1") (pintype "passive"))
      (node (ref "Q17") (pin "4") (pinfunction "S2_4") (pintype "passive"))
      (node (ref "Q18") (pin "1") (pinfunction "S1_1") (pintype "passive"))
      (node (ref "Q25") (pin "1") (pinfunction "S1_1") (pintype "passive"))
      (node (ref "R60") (pin "1") (pinfunction "1_1") (pintype "passive"))
      (node (ref "R61") (pin "1") (pinfunction "1_1") (pintype "passive"))
      (node (ref "R65") (pin "1") (pinfunction "1_1") (pintype "passive"))
      (node (ref "R79") (pin "1") (pinfunction "1_1") (pintype "passive"))
      (node (ref "U13") (pin "A1") (pinfunction "VSS_A1") (pintype "power_in"))
      (node (ref "U13") (pin "A9") (pinfunction "VSS_A9") (pintype "power_in"))
      (node (ref "U13") (pin "B2") (pinfunction "VSS_B2") (pintype "power_in"))
      (node (ref "U13") (pin "B8") (pinfunction "VSS_B8") (pintype "power_in"))
      (node (ref "U13") (pin "E4") (pinfunction "VSS_E4") (pintype "power_in"))
      (node (ref "U13") (pin "E5") (pinfunction "VSS_E5") (pintype "power_in"))
      (node (ref "U13") (pin "F4") (pinfunction "VSS_F4") (pintype "power_in"))
      (node (ref "U13") (pin "F5") (pinfunction "VSS_F5") (pintype "power_in"))
      (node (ref "U13") (pin "K2") (pinfunction "VSS_K2") (pintype "power_in"))
      (node (ref "U13") (pin "K3") (pinfunction "VSS_K3") (pintype "power_in"))
      (node (ref "U13") (pin "K5") (pinfunction "VSS_K5") (pintype "power_in"))
      (node (ref "U13") (pin "K7") (pinfunction "VSS_K7") (pintype "power_in"))
      (node (ref "U13") (pin "K8") (pinfunction "VSS_K8") (pintype "power_in"))
      (node (ref "U13") (pin "L1") (pinfunction "VSS_L1") (pintype "power_in"))
      (node (ref "U13") (pin "L9") (pinfunction "VSS_L9") (pintype "power_in"))
      (node (ref "U13") (pin "M1") (pinfunction "VSS_M1") (pintype "power_in"))
      (node (ref "U13") (pin "M2") (pinfunction "VSS_M2") (pintype "power_in"))
      (node (ref "U13") (pin "M8") (pinfunction "VSS_M8") (pintype "power_in"))
      (node (ref "U13") (pin "M9") (pinfunction "VSS_M9") (pintype "power_in"))
      (node (ref "U7") (pin "4") (pinfunction "GND_4") (pintype "power_in"))
      (node (ref "U9") (pin "15") (pinfunction "DIR2_15") (pintype "input"))
      (node (ref "U9") (pin "7") (pinfunction "DIR4_7") (pintype "input"))
      (node (ref "U9") (pin "8") (pinfunction "GND_8") (pintype "power_in"))
      (node (ref "U9") (pin "9") (pinfunction "~{OE}_9") (pintype "input"))
    )
    (net (code "66") (name "Net-(D13-Anode)") (class "Default")
      (node (ref "D13") (pin "A") (pinfunction "Anode_A") (pintype "passive"))
      (node (ref "R38") (pin "1") (pinfunction "1_1") (pintype "passive"))
    )
    (net (code "67") (name "Net-(D14-Anode)") (class "Default")
      (node (ref "D14") (pin "A") (pinfunction "Anode_A") (pintype "passive"))
      (node (ref "R39") (pin "1") (pinfunction "1_1") (pintype "passive"))
    )
    (net (code "68") (name "Net-(Q12A-D1)") (class "Default")
      (node (ref "Q12") (pin "6") (pinfunction "D1_6") (pintype "passive"))
      (node (ref "R38") (pin "2") (pinfunction "2_2") (pintype "passive"))
    )
    (net (code "69") (name "Net-(Q12B-D2)") (class "Default")
      (node (ref "Q12") (pin "3") (pinfunction "D2_3") (pintype "passive"))
      (node (ref "R39") (pin "2") (pinfunction "2_2") (pintype "passive"))
    )
    (net (code "70") (name "Net-(Q16A-D1)") (class "Default")
      (node (ref "Q16") (pin "6") (pinfunction "D1_6") (pintype "passive"))
      (node (ref "R62") (pin "1") (pinfunction "1_1") (pintype "passive"))
    )
    (net (code "71") (name "Net-(Q17A-D1)") (class "Default")
      (node (ref "Q17") (pin "6") (pinfunction "D1_6") (pintype "passive"))
      (node (ref "R66") (pin "1") (pinfunction "1_1") (pintype "passive"))
    )
    (net (code "72") (name "Net-(Q17B-D2)") (class "Default")
      (node (ref "Q17") (pin "3") (pinfunction "D2_3") (pintype "passive"))
      (node (ref "R64") (pin "1") (pinfunction "1_1") (pintype "passive"))
    )
    (net (code "73") (name "Net-(Q18A-D1)") (class "Default")
      (node (ref "Q18") (pin "5") (pinfunction "G2_5") (pintype "passive"))
      (node (ref "Q18") (pin "6") (pinfunction "D1_6") (pintype "passive"))
      (node (ref "R80") (pin "2") (pinfunction "2_2") (pintype "passive"))
    )
    (net (code "74") (name "Net-(Q18B-D2)") (class "Default")
      (node (ref "C76") (pin "2") (pinfunction "2_2") (pintype "passive"))
      (node (ref "Q18") (pin "3") (pinfunction "D2_3") (pintype "passive"))
      (node (ref "U13") (pin "B9") (pinfunction "VBUS_B9") (pintype "power_in"))
    )
    (net (code "75") (name "Net-(Q25A-G1)") (class "Default")
      (node (ref "NC12") (pin "1") (pinfunction "1_1") (pintype "passive"))
      (node (ref "Q25") (pin "2") (pinfunction "G1_2") (pintype "passive"))
    )
    (net (code "76") (name "Net-(RGB2-B)") (class "Default")
      (node (ref "R66") (pin "2") (pinfunction "2_2") (pintype "passive"))
      (node (ref "RGB2") (pin "3") (pinfunction "B_3") (pintype "passive"))
    )
    (net (code "77") (name "Net-(RGB2-G)") (class "Default")
      (node (ref "R64") (pin "2") (pinfunction "2_2") (pintype "passive"))
      (node (ref "RGB2") (pin "2") (pinfunction "G_2") (pintype "passive"))
    )
    (net (code "78") (name "Net-(RGB2-R)") (class "Default")
      (node (ref "R62") (pin "2") (pinfunction "2_2") (pintype "passive"))
      (node (ref "RGB2") (pin "1") (pinfunction "R_1") (pintype "passive"))
    )
    (net (code "79") (name "VBUS") (class "Default")
      (node (ref "Q18") (pin "4") (pinfunction "S2_4") (pintype "passive"))
      (node (ref "R80") (pin "1") (pinfunction "1_1") (pintype "passive"))
    )
    (net (code "80") (name "VDD_NORA") (class "Default")
      (node (ref "C69") (pin "2") (pinfunction "2_2") (pintype "passive"))
      (node (ref "C70") (pin "2") (pinfunction "2_2") (pintype "passive"))
      (node (ref "C86") (pin "1") (pinfunction "1_1") (pintype "passive"))
      (node (ref "J4") (pin "2") (pinfunction "2_2") (pintype "passive"))
      (node (ref "NC9") (pin "1") (pinfunction "1_1") (pintype "passive"))
      (node (ref "Q18") (pin "2") (pinfunction "G1_2") (pintype "passive"))
      (node (ref "R79") (pin "2") (pinfunction "2_2") (pintype "passive"))
      (node (ref "TP36") (pin "1") (pintype "passive"))
      (node (ref "U13") (pin "A7") (pinfunction "VDD_A7") (pintype "power_in"))
      (node (ref "U13") (pin "A8") (pinfunction "VDDH_A8") (pintype "power_in"))
      (node (ref "U13") (pin "B7") (pinfunction "VDD_B7") (pintype "power_in"))
    )
    (net (code "81") (name "unconnected-(J11-KEY-Pad7)") (class "Default")
      (node (ref "J11") (pin "7") (pinfunction "KEY_7") (pintype "passive+no_connect"))
    )
    (net (code "82") (name "unconnected-(J11-TDI-Pad8)") (class "Default")
      (node (ref "J11") (pin "8") (pinfunction "TDI_8") (pintype "passive+no_connect"))
    )
    (net (code "83") (name "unconnected-(J13-Pad1)") (class "Default")
      (node (ref "J13") (pin "1") (pinfunction "1_1") (pintype "passive+no_connect"))
    )
    (net (code "84") (name "unconnected-(J13-Pad3)") (class "Default")
      (node (ref "J13") (pin "3") (pinfunction "3_3") (pintype "passive+no_connect"))
    )
    (net (code "85") (name "unconnected-(J13-Pad5)") (class "Default")
      (node (ref "J13") (pin "5") (pinfunction "5_5") (pintype "passive+no_connect"))
    )
    (net (code "86") (name "unconnected-(Q16B-D2-Pad3)") (class "Default")
      (node (ref "Q16") (pin "3") (pinfunction "D2_3") (pintype "passive+no_connect"))
    )
    (net (code "87") (name "unconnected-(U9-A1-Pad3)") (class "Default")
      (node (ref "U9") (pin "3") (pinfunction "A1_3") (pintype "bidirectional"))
    )
    (net (code "88") (name "unconnected-(U9-A2-Pad4)") (class "Default")
      (node (ref "U9") (pin "4") (pinfunction "A2_4") (pintype "bidirectional"))
    )
    (net (code "89") (name "unconnected-(U9-A3-Pad5)") (class "Default")
      (node (ref "U9") (pin "5") (pinfunction "A3_5") (pintype "bidirectional"))
    )
    (net (code "90") (name "unconnected-(U9-A4-Pad6)") (class "Default")
      (node (ref "U9") (pin "6") (pinfunction "A4_6") (pintype "bidirectional"))
    )
    (net (code "91") (name "unconnected-(U13A-NC-PadA6)") (class "Default")
      (node (ref "U13") (pin "A6") (pinfunction "NC_A6") (pintype "tri_state+no_connect"))
    )
    (net (code "92") (name "unconnected-(U13A-NC-PadJ1)") (class "Default")
      (node (ref "U13") (pin "J1") (pinfunction "NC_J1") (pintype "tri_state+no_connect"))
    )
    (net (code "93") (name "unconnected-(U13A-NC-PadJ4)") (class "Default")
      (node (ref "U13") (pin "J4") (pinfunction "NC_J4") (pintype "tri_state+no_connect"))
    )
    (net (code "94") (name "unconnected-(U13A-NC-PadJ5)") (class "Default")
      (node (ref "U13") (pin "J5") (pinfunction "NC_J5") (pintype "tri_state+no_connect"))
    )
    (net (code "95") (name "unconnected-(U13A-NC-PadK1)") (class "Default")
      (node (ref "U13") (pin "K1") (pinfunction "NC_K1") (pintype "tri_state+no_connect"))
    )
    (net (code "96") (name "unconnected-(U13A-NC-PadK9)") (class "Default")
      (node (ref "U13") (pin "K9") (pinfunction "NC_K9") (pintype "tri_state+no_connect"))
    )
  )
)
